# MainSensor.net
KiCad netlist of a schematic drawn in EAGLE
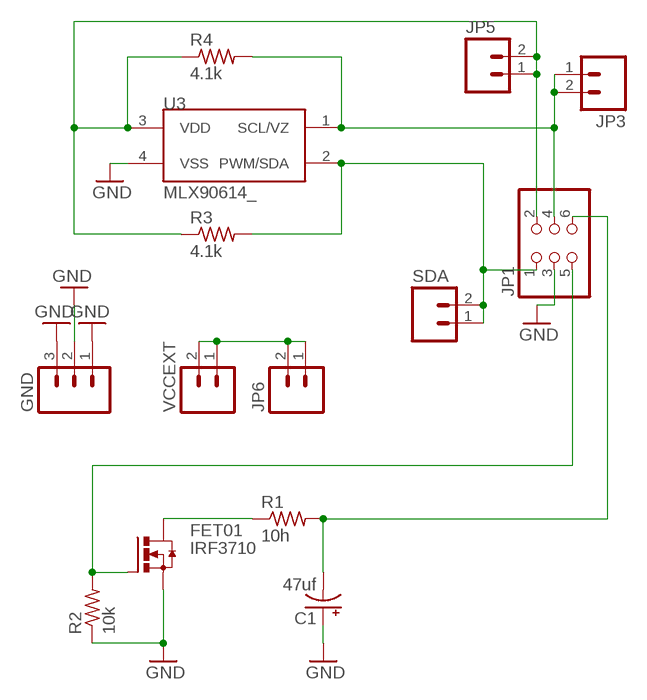
[diagram p0: schematic, sheet 1]

(export (version "E")
  (design (tool "Eeschema 10.0.6"))
  (components
    (comp (ref "C1")
      (value "47uf")
      (footprint "eagle-import:E2,5-6E")
      (libsource (lib "eagle-import") (part "CPOL-USE2,5-6E"))
    )
    (comp (ref "FET01")
      (value "IRF3710")
      (footprint "eagle-import:TO220AH")
      (libsource (lib "eagle-import") (part "IRF3704"))
    )
    (comp (ref "GND")
      (value "M03LONGPADS")
      (footprint "eagle-import:1X03_LONGPADS")
      (libsource (lib "eagle-import") (part "M03LONGPADS"))
    )
    (comp (ref "JP1")
      (value "PINHD-2X3")
      (footprint "eagle-import:2X03")
      (libsource (lib "eagle-import") (part "PINHD-2X3"))
    )
    (comp (ref "JP3")
      (value "M02LOCK_LONGPADS")
      (footprint "eagle-import:1X02_LOCK_LONGPADS")
      (libsource (lib "eagle-import") (part "M02LOCK_LONGPADS"))
    )
    (comp (ref "JP5")
      (value "M02LOCK_LONGPADS")
      (footprint "eagle-import:1X02_LOCK_LONGPADS")
      (libsource (lib "eagle-import") (part "M02LOCK_LONGPADS"))
    )
    (comp (ref "JP6")
      (value "M02LOCK_LONGPADS")
      (footprint "eagle-import:1X02_LOCK_LONGPADS")
      (libsource (lib "eagle-import") (part "M02LOCK_LONGPADS"))
    )
    (comp (ref "R1")
      (value "10h")
      (footprint "eagle-import:0207_7")
      (libsource (lib "eagle-import") (part "R-US_0207/7"))
    )
    (comp (ref "R2")
      (value "10k")
      (footprint "eagle-import:0207_7")
      (libsource (lib "eagle-import") (part "R-US_0207/7"))
    )
    (comp (ref "R3")
      (value "4.1k")
      (footprint "eagle-import:0204_5")
      (libsource (lib "eagle-import") (part "R-US_0204/5"))
    )
    (comp (ref "R4")
      (value "4.1k")
      (footprint "eagle-import:0204_5")
      (libsource (lib "eagle-import") (part "R-US_0204/5"))
    )
    (comp (ref "SDA")
      (value "M02LOCK_LONGPADS")
      (footprint "eagle-import:1X02_LOCK_LONGPADS")
      (libsource (lib "eagle-import") (part "M02LOCK_LONGPADS"))
    )
    (comp (ref "U3")
      (value "MLX90614_")
      (footprint "eagle-import:TO-39")
      (libsource (lib "eagle-import") (part "MLX90614_"))
    )
    (comp (ref "VCCEXT")
      (value "M02LOCK_LONGPADS")
      (footprint "eagle-import:1X02_LOCK_LONGPADS")
      (libsource (lib "eagle-import") (part "M02LOCK_LONGPADS"))
    )
  )
  (nets
    (net (code "1") (name "GND") (class "Default")
      (node (ref "C1") (pin "+") (pinfunction "+_+") (pintype "passive"))
      (node (ref "FET01") (pin "E") (pinfunction "S_E") (pintype "passive"))
      (node (ref "GND") (pin "1") (pinfunction "1_1") (pintype "passive"))
      (node (ref "GND") (pin "2") (pinfunction "2_2") (pintype "passive"))
      (node (ref "GND") (pin "3") (pinfunction "3_3") (pintype "passive"))
      (node (ref "JP1") (pin "3") (pinfunction "3_3") (pintype "passive"))
      (node (ref "R2") (pin "1") (pinfunction "1_1") (pintype "passive"))
      (node (ref "U3") (pin "4") (pinfunction "VSS_4") (pintype "bidirectional"))
    )
    (net (code "2") (name "Net-(C1-Pad-)") (class "Default")
      (node (ref "C1") (pin "-") (pinfunction "-_-") (pintype "passive"))
      (node (ref "JP1") (pin "6") (pinfunction "6_6") (pintype "passive"))
      (node (ref "R1") (pin "2") (pinfunction "2_2") (pintype "passive"))
    )
    (net (code "3") (name "Net-(FET01-D)") (class "Default")
      (node (ref "FET01") (pin "C") (pinfunction "D_C") (pintype "passive"))
      (node (ref "R1") (pin "1") (pinfunction "1_1") (pintype "passive"))
    )
    (net (code "4") (name "Net-(FET01-G)") (class "Default")
      (node (ref "FET01") (pin "B") (pinfunction "G_B") (pintype "passive"))
      (node (ref "JP1") (pin "5") (pinfunction "5_5") (pintype "passive"))
      (node (ref "R2") (pin "2") (pinfunction "2_2") (pintype "passive"))
    )
    (net (code "5") (name "Net-(JP6-Pad1)") (class "Default")
      (node (ref "JP6") (pin "1") (pinfunction "1_1") (pintype "passive"))
      (node (ref "JP6") (pin "2") (pinfunction "2_2") (pintype "passive"))
      (node (ref "VCCEXT") (pin "1") (pinfunction "1_1") (pintype "passive"))
      (node (ref "VCCEXT") (pin "2") (pinfunction "2_2") (pintype "passive"))
    )
    (net (code "6") (name "Net-(U3-PWM{slash}SDA)") (class "Default")
      (node (ref "JP1") (pin "1") (pinfunction "1_1") (pintype "passive"))
      (node (ref "R3") (pin "2") (pinfunction "2_2") (pintype "passive"))
      (node (ref "SDA") (pin "1") (pinfunction "1_1") (pintype "passive"))
      (node (ref "SDA") (pin "2") (pinfunction "2_2") (pintype "passive"))
      (node (ref "U3") (pin "2") (pinfunction "PWM/SDA_2") (pintype "bidirectional"))
    )
    (net (code "7") (name "Net-(U3-SCL{slash}VZ)") (class "Default")
      (node (ref "JP1") (pin "4") (pinfunction "4_4") (pintype "passive"))
      (node (ref "JP3") (pin "1") (pinfunction "1_1") (pintype "passive"))
      (node (ref "JP3") (pin "2") (pinfunction "2_2") (pintype "passive"))
      (node (ref "R4") (pin "2") (pinfunction "2_2") (pintype "passive"))
      (node (ref "U3") (pin "1") (pinfunction "SCL/VZ_1") (pintype "bidirectional"))
    )
    (net (code "8") (name "Net-(U3-VDD)") (class "Default")
      (node (ref "JP1") (pin "2") (pinfunction "2_2") (pintype "passive"))
      (node (ref "JP5") (pin "1") (pinfunction "1_1") (pintype "passive"))
      (node (ref "JP5") (pin "2") (pinfunction "2_2") (pintype "passive"))
      (node (ref "R3") (pin "1") (pinfunction "1_1") (pintype "passive"))
      (node (ref "R4") (pin "1") (pinfunction "1_1") (pintype "passive"))
      (node (ref "U3") (pin "3") (pinfunction "VDD_3") (pintype "bidirectional"))
    )
  )
)
